# controller2_5.net
KiCad netlist of a schematic drawn in EAGLE
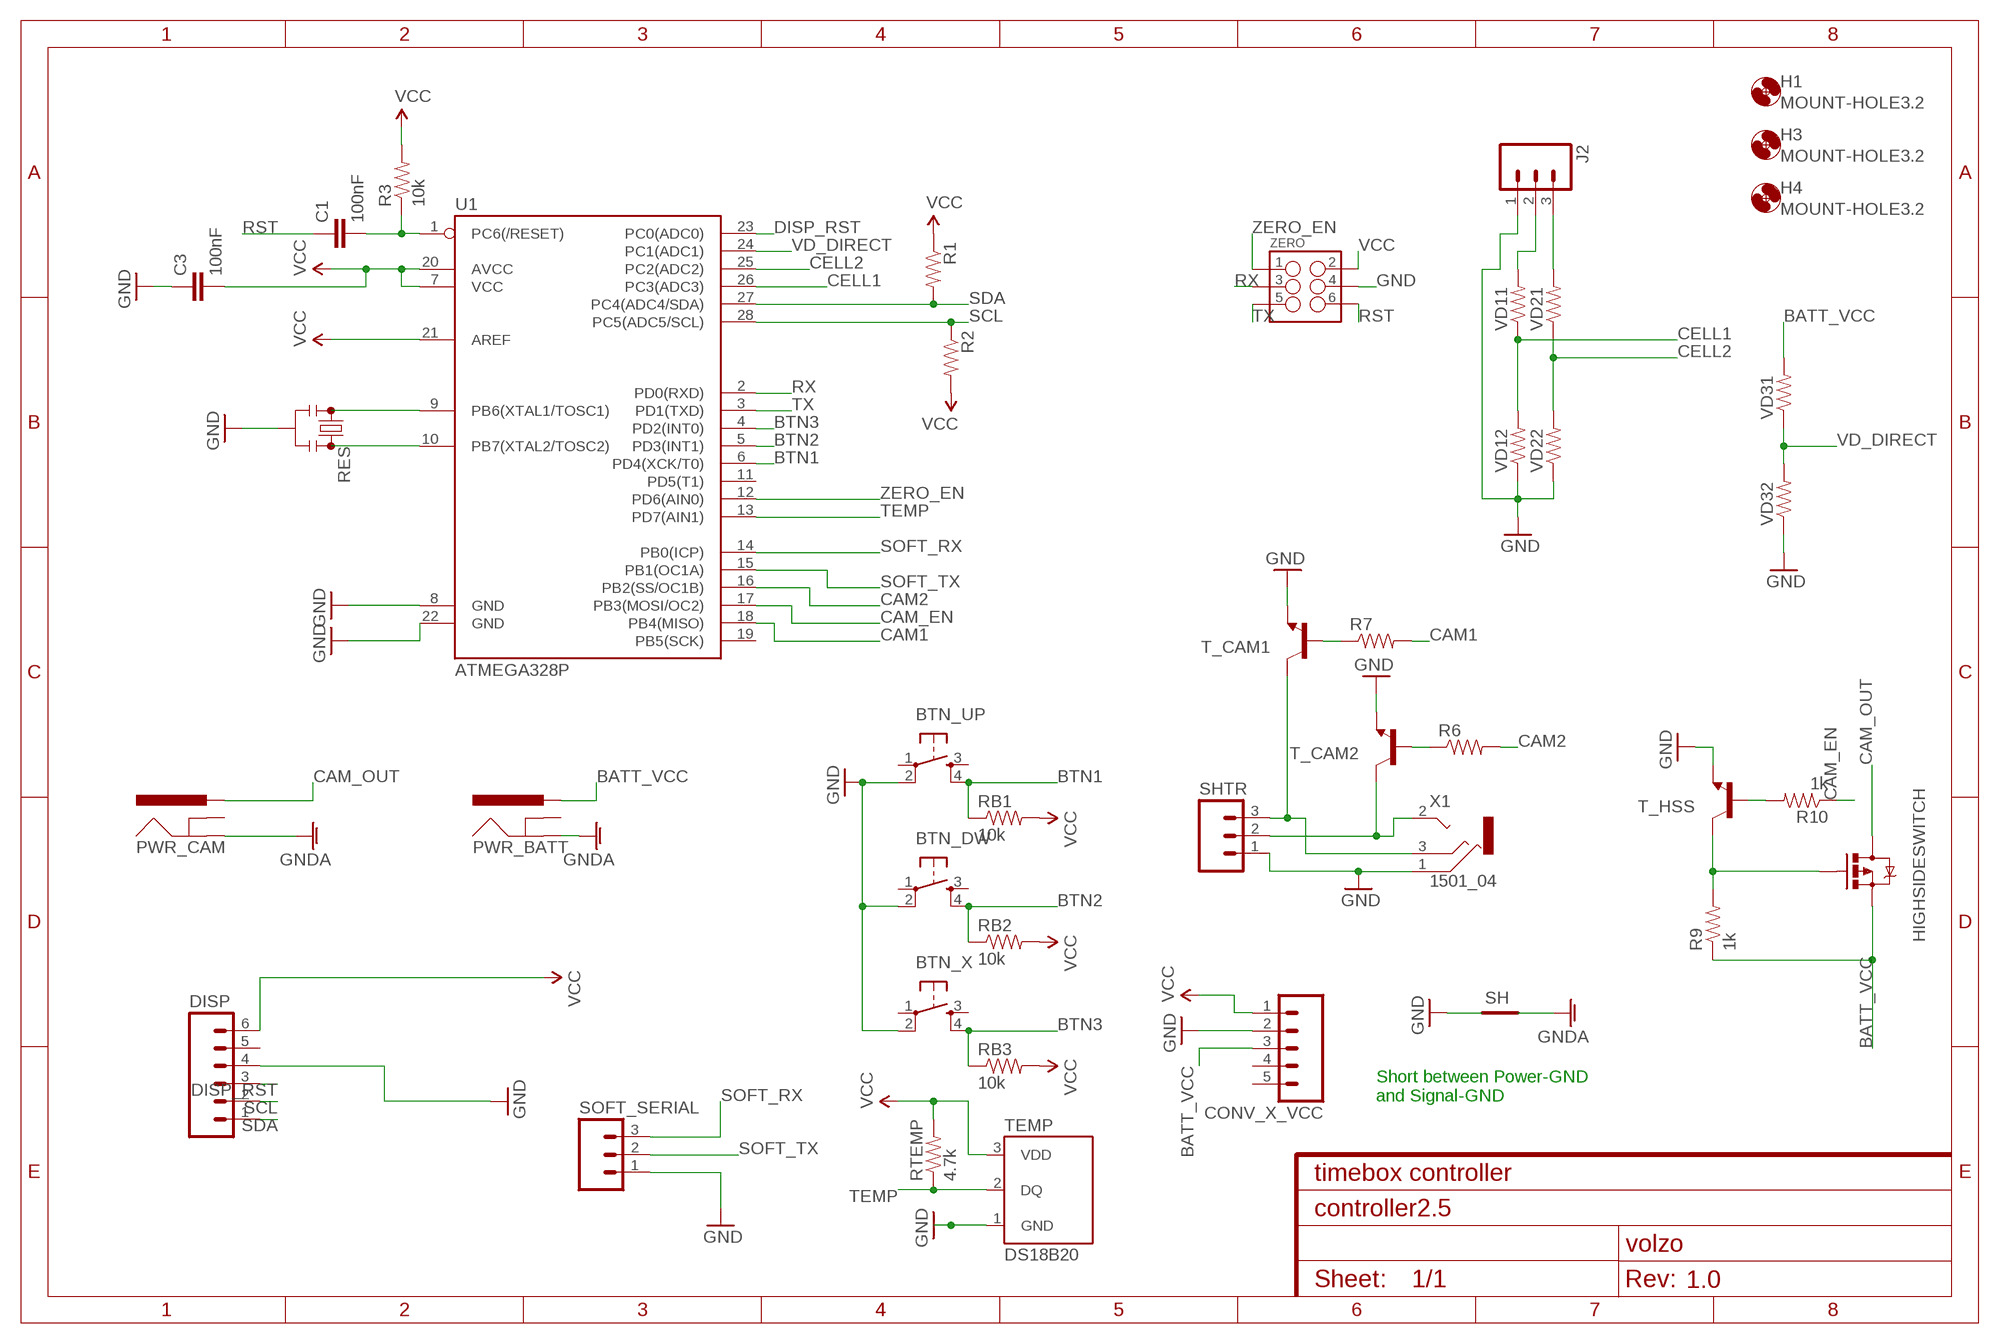
[diagram p0: schematic, sheet 1]

(export (version "E")
  (design (tool "Eeschema 10.0.6"))
  (components
    (comp (ref "BTN_DW")
      (value "TAC_SWITCHPTH")
      (footprint "eagle-import:TACTILE-PTH")
      (libsource (lib "eagle-import") (part "TAC_SWITCHPTH"))
    )
    (comp (ref "BTN_UP")
      (value "TAC_SWITCHPTH")
      (footprint "eagle-import:TACTILE-PTH")
      (libsource (lib "eagle-import") (part "TAC_SWITCHPTH"))
    )
    (comp (ref "BTN_X")
      (value "TAC_SWITCHPTH")
      (footprint "eagle-import:TACTILE-PTH")
      (libsource (lib "eagle-import") (part "TAC_SWITCHPTH"))
    )
    (comp (ref "C1")
      (value "100nF")
      (footprint "eagle-import:CAP-PTH-SMALL")
      (libsource (lib "eagle-import") (part "CAPPTH"))
    )
    (comp (ref "C3")
      (value "100nF")
      (footprint "eagle-import:CAP-PTH-SMALL")
      (libsource (lib "eagle-import") (part "CAPPTH"))
    )
    (comp (ref "CONV_X_VCC")
      (value "M05LOCK")
      (footprint "eagle-import:1X05_LOCK")
      (libsource (lib "eagle-import") (part "M05LOCK"))
    )
    (comp (ref "DISP")
      (value "M06FEMALE_LOCK")
      (footprint "eagle-import:1X06_FEMALE_LOCK.010")
      (libsource (lib "eagle-import") (part "M06FEMALE_LOCK"))
    )
    (comp (ref "H1")
      (value "MOUNT-HOLE3.2")
      (footprint "eagle-import:3,2")
      (libsource (lib "eagle-import") (part "MOUNT-HOLE3.2"))
    )
    (comp (ref "H3")
      (value "MOUNT-HOLE3.2")
      (footprint "eagle-import:3,2")
      (libsource (lib "eagle-import") (part "MOUNT-HOLE3.2"))
    )
    (comp (ref "H4")
      (value "MOUNT-HOLE3.2")
      (footprint "eagle-import:3,2")
      (libsource (lib "eagle-import") (part "MOUNT-HOLE3.2"))
    )
    (comp (ref "HIGHSIDESWITCH")
      (value "MOSFET-PCHANNELNDP6020P_20V_24A_LOW_VGS_TH")
      (footprint "eagle-import:TO220V")
      (libsource (lib "eagle-import") (part "MOSFET-PCHANNELNDP6020P_20V_24A_LOW_VGS_TH"))
    )
    (comp (ref "J2")
      (value "M03LOCK")
      (footprint "eagle-import:1X03_LOCK")
      (libsource (lib "eagle-import") (part "M03LOCK"))
    )
    (comp (ref "PWR_BATT")
      (value "POWER_JACKPTH_BREAD")
      (footprint "eagle-import:POWER_JACK_PTH_BREAD")
      (libsource (lib "eagle-import") (part "POWER_JACKPTH_BREAD"))
    )
    (comp (ref "PWR_CAM")
      (value "POWER_JACKPTH_BREAD")
      (footprint "eagle-import:POWER_JACK_PTH_BREAD")
      (libsource (lib "eagle-import") (part "POWER_JACKPTH_BREAD"))
    )
    (comp (ref "R1")
      (value "RESISTORAXIAL-0.3")
      (footprint "eagle-import:AXIAL-0.3")
      (libsource (lib "eagle-import") (part "RESISTORAXIAL-0.3"))
    )
    (comp (ref "R2")
      (value "RESISTORAXIAL-0.3")
      (footprint "eagle-import:AXIAL-0.3")
      (libsource (lib "eagle-import") (part "RESISTORAXIAL-0.3"))
    )
    (comp (ref "R3")
      (value "10k")
      (footprint "eagle-import:AXIAL-0.3")
      (libsource (lib "eagle-import") (part "RESISTORAXIAL-0.3"))
    )
    (comp (ref "R6")
      (value "RESISTORAXIAL-0.3")
      (footprint "eagle-import:AXIAL-0.3")
      (libsource (lib "eagle-import") (part "RESISTORAXIAL-0.3"))
    )
    (comp (ref "R7")
      (value "RESISTORAXIAL-0.3")
      (footprint "eagle-import:AXIAL-0.3")
      (libsource (lib "eagle-import") (part "RESISTORAXIAL-0.3"))
    )
    (comp (ref "R9")
      (value "1k")
      (footprint "eagle-import:AXIAL-0.3")
      (libsource (lib "eagle-import") (part "RESISTORAXIAL-0.3"))
    )
    (comp (ref "R10")
      (value "1k")
      (footprint "eagle-import:AXIAL-0.3")
      (libsource (lib "eagle-import") (part "RESISTORAXIAL-0.3"))
    )
    (comp (ref "RB1")
      (value "10k")
      (footprint "eagle-import:AXIAL-0.3")
      (libsource (lib "eagle-import") (part "RESISTORAXIAL-0.3"))
    )
    (comp (ref "RB2")
      (value "10k")
      (footprint "eagle-import:AXIAL-0.3")
      (libsource (lib "eagle-import") (part "RESISTORAXIAL-0.3"))
    )
    (comp (ref "RB3")
      (value "10k")
      (footprint "eagle-import:AXIAL-0.3")
      (libsource (lib "eagle-import") (part "RESISTORAXIAL-0.3"))
    )
    (comp (ref "RES")
      (value "RESONATORPTH")
      (footprint "eagle-import:RESONATOR-PTH")
      (libsource (lib "eagle-import") (part "RESONATORPTH"))
    )
    (comp (ref "RTEMP")
      (value "4.7k")
      (footprint "eagle-import:AXIAL-0.3")
      (libsource (lib "eagle-import") (part "RESISTORAXIAL-0.3"))
    )
    (comp (ref "SH")
      (value "SHORT-HT5")
      (footprint "eagle-import:SHORT_TOP-50")
      (libsource (lib "eagle-import") (part "SHORT-HT5"))
    )
    (comp (ref "SHTR")
      (value "M03LOCK")
      (footprint "eagle-import:1X03_LOCK")
      (libsource (lib "eagle-import") (part "M03LOCK"))
    )
    (comp (ref "SOFT_SERIAL")
      (value "M03LOCK")
      (footprint "eagle-import:1X03_LOCK")
      (libsource (lib "eagle-import") (part "M03LOCK"))
    )
    (comp (ref "TEMP")
      (value "DS18B20")
      (footprint "eagle-import:TO-92-AMMO")
      (libsource (lib "eagle-import") (part "DS18B20"))
    )
    (comp (ref "T_CAM1")
      (value "TRANSISTOR_NPN2N3904")
      (footprint "eagle-import:TO-92")
      (libsource (lib "eagle-import") (part "TRANSISTOR_NPN2N3904"))
    )
    (comp (ref "T_CAM2")
      (value "TRANSISTOR_NPN2N3904")
      (footprint "eagle-import:TO-92")
      (libsource (lib "eagle-import") (part "TRANSISTOR_NPN2N3904"))
    )
    (comp (ref "T_HSS")
      (value "TRANSISTOR_NPN2N3904")
      (footprint "eagle-import:TO-92")
      (libsource (lib "eagle-import") (part "TRANSISTOR_NPN2N3904"))
    )
    (comp (ref "U1")
      (value "ATMEGA328P")
      (footprint "eagle-import:DIL28-3")
      (libsource (lib "eagle-import") (part "ATMEGA328P_PDIP"))
    )
    (comp (ref "VD11")
      (value "RESISTORAXIAL-0.3")
      (footprint "eagle-import:AXIAL-0.3")
      (libsource (lib "eagle-import") (part "RESISTORAXIAL-0.3"))
    )
    (comp (ref "VD12")
      (value "RESISTORAXIAL-0.3")
      (footprint "eagle-import:AXIAL-0.3")
      (libsource (lib "eagle-import") (part "RESISTORAXIAL-0.3"))
    )
    (comp (ref "VD21")
      (value "RESISTORAXIAL-0.3")
      (footprint "eagle-import:AXIAL-0.3")
      (libsource (lib "eagle-import") (part "RESISTORAXIAL-0.3"))
    )
    (comp (ref "VD22")
      (value "RESISTORAXIAL-0.3")
      (footprint "eagle-import:AXIAL-0.3")
      (libsource (lib "eagle-import") (part "RESISTORAXIAL-0.3"))
    )
    (comp (ref "VD31")
      (value "RESISTORAXIAL-0.3")
      (footprint "eagle-import:AXIAL-0.3")
      (libsource (lib "eagle-import") (part "RESISTORAXIAL-0.3"))
    )
    (comp (ref "VD32")
      (value "RESISTORAXIAL-0.3")
      (footprint "eagle-import:AXIAL-0.3")
      (libsource (lib "eagle-import") (part "RESISTORAXIAL-0.3"))
    )
    (comp (ref "X1")
      (value "1501_04")
      (footprint "eagle-import:1501_05")
      (libsource (lib "eagle-import") (part "1501_04"))
    )
    (comp (ref "ZERO")
      (value "M03X2FEMALE")
      (footprint "eagle-import:2X3")
      (libsource (lib "eagle-import") (part "M03X2FEMALE"))
    )
  )
  (nets
    (net (code "1") (name "/BATT_VCC") (class "Default")
      (node (ref "CONV_X_VCC") (pin "3") (pinfunction "3_3") (pintype "passive"))
      (node (ref "HIGHSIDESWITCH") (pin "3") (pinfunction "S_3") (pintype "passive"))
      (node (ref "PWR_BATT") (pin "PWR") (pinfunction "PWR_PWR") (pintype "bidirectional"))
      (node (ref "R9") (pin "P$1") (pinfunction "1_P$1") (pintype "passive"))
      (node (ref "VD31") (pin "P$2") (pinfunction "2_P$2") (pintype "passive"))
    )
    (net (code "2") (name "/BTN1") (class "Default")
      (node (ref "BTN_UP") (pin "4") (pinfunction "4_4") (pintype "passive"))
      (node (ref "RB1") (pin "P$1") (pinfunction "1_P$1") (pintype "passive"))
      (node (ref "U1") (pin "6") (pinfunction "PD4(XCK/T0)_6") (pintype "bidirectional"))
    )
    (net (code "3") (name "/BTN2") (class "Default")
      (node (ref "BTN_DW") (pin "4") (pinfunction "4_4") (pintype "passive"))
      (node (ref "RB2") (pin "P$1") (pinfunction "1_P$1") (pintype "passive"))
      (node (ref "U1") (pin "5") (pinfunction "PD3(INT1)_5") (pintype "bidirectional"))
    )
    (net (code "4") (name "/BTN3") (class "Default")
      (node (ref "BTN_X") (pin "4") (pinfunction "4_4") (pintype "passive"))
      (node (ref "RB3") (pin "P$1") (pinfunction "1_P$1") (pintype "passive"))
      (node (ref "U1") (pin "4") (pinfunction "PD2(INT0)_4") (pintype "bidirectional"))
    )
    (net (code "5") (name "/CAM1") (class "Default")
      (node (ref "R7") (pin "P$2") (pinfunction "2_P$2") (pintype "passive"))
      (node (ref "U1") (pin "18") (pinfunction "PB4(MISO)_18") (pintype "bidirectional"))
    )
    (net (code "6") (name "/CAM2") (class "Default")
      (node (ref "R6") (pin "P$2") (pinfunction "2_P$2") (pintype "passive"))
      (node (ref "U1") (pin "16") (pinfunction "PB2(SS/OC1B)_16") (pintype "bidirectional"))
    )
    (net (code "7") (name "/CAM_EN") (class "Default")
      (node (ref "R10") (pin "P$1") (pinfunction "1_P$1") (pintype "passive"))
      (node (ref "U1") (pin "17") (pinfunction "PB3(MOSI/OC2)_17") (pintype "bidirectional"))
    )
    (net (code "8") (name "/CAM_OUT") (class "Default")
      (node (ref "HIGHSIDESWITCH") (pin "2") (pinfunction "D_2") (pintype "passive"))
      (node (ref "PWR_CAM") (pin "PWR") (pinfunction "PWR_PWR") (pintype "bidirectional"))
    )
    (net (code "9") (name "/CELL1") (class "Default")
      (node (ref "U1") (pin "26") (pinfunction "PC3(ADC3)_26") (pintype "bidirectional"))
      (node (ref "VD11") (pin "P$1") (pinfunction "1_P$1") (pintype "passive"))
      (node (ref "VD12") (pin "P$2") (pinfunction "2_P$2") (pintype "passive"))
    )
    (net (code "10") (name "/CELL2") (class "Default")
      (node (ref "U1") (pin "25") (pinfunction "PC2(ADC2)_25") (pintype "bidirectional"))
      (node (ref "VD21") (pin "P$1") (pinfunction "1_P$1") (pintype "passive"))
      (node (ref "VD22") (pin "P$2") (pinfunction "2_P$2") (pintype "passive"))
    )
    (net (code "11") (name "/DISP_RST") (class "Default")
      (node (ref "DISP") (pin "3") (pinfunction "3_3") (pintype "passive"))
      (node (ref "U1") (pin "23") (pinfunction "PC0(ADC0)_23") (pintype "bidirectional"))
    )
    (net (code "12") (name "/RST") (class "Default")
      (node (ref "C1") (pin "1") (pinfunction "1_1") (pintype "passive"))
      (node (ref "ZERO") (pin "6") (pinfunction "6_6") (pintype "bidirectional"))
    )
    (net (code "13") (name "/RX") (class "Default")
      (node (ref "U1") (pin "2") (pinfunction "PD0(RXD)_2") (pintype "bidirectional"))
      (node (ref "ZERO") (pin "3") (pinfunction "3_3") (pintype "bidirectional"))
    )
    (net (code "14") (name "/SCL") (class "Default")
      (node (ref "DISP") (pin "2") (pinfunction "2_2") (pintype "passive"))
      (node (ref "R2") (pin "P$1") (pinfunction "1_P$1") (pintype "passive"))
      (node (ref "U1") (pin "28") (pinfunction "PC5(ADC5/SCL)_28") (pintype "bidirectional"))
    )
    (net (code "15") (name "/SDA") (class "Default")
      (node (ref "DISP") (pin "1") (pinfunction "1_1") (pintype "passive"))
      (node (ref "R1") (pin "P$2") (pinfunction "2_P$2") (pintype "passive"))
      (node (ref "U1") (pin "27") (pinfunction "PC4(ADC4/SDA)_27") (pintype "bidirectional"))
    )
    (net (code "16") (name "/SOFT_RX") (class "Default")
      (node (ref "SOFT_SERIAL") (pin "3") (pinfunction "3_3") (pintype "passive"))
      (node (ref "U1") (pin "14") (pinfunction "PB0(ICP)_14") (pintype "bidirectional"))
    )
    (net (code "17") (name "/SOFT_TX") (class "Default")
      (node (ref "SOFT_SERIAL") (pin "2") (pinfunction "2_2") (pintype "passive"))
      (node (ref "U1") (pin "15") (pinfunction "PB1(OC1A)_15") (pintype "bidirectional"))
    )
    (net (code "18") (name "/TEMP") (class "Default")
      (node (ref "RTEMP") (pin "P$1") (pinfunction "1_P$1") (pintype "passive"))
      (node (ref "TEMP") (pin "2") (pinfunction "DQ_2") (pintype "bidirectional"))
      (node (ref "U1") (pin "13") (pinfunction "PD7(AIN1)_13") (pintype "bidirectional"))
    )
    (net (code "19") (name "/TX") (class "Default")
      (node (ref "U1") (pin "3") (pinfunction "PD1(TXD)_3") (pintype "bidirectional"))
      (node (ref "ZERO") (pin "5") (pinfunction "5_5") (pintype "bidirectional"))
    )
    (net (code "20") (name "/VD_DIRECT") (class "Default")
      (node (ref "U1") (pin "24") (pinfunction "PC1(ADC1)_24") (pintype "bidirectional"))
      (node (ref "VD31") (pin "P$1") (pinfunction "1_P$1") (pintype "passive"))
      (node (ref "VD32") (pin "P$2") (pinfunction "2_P$2") (pintype "passive"))
    )
    (net (code "21") (name "/ZERO_EN") (class "Default")
      (node (ref "U1") (pin "12") (pinfunction "PD6(AIN0)_12") (pintype "bidirectional"))
      (node (ref "ZERO") (pin "1") (pinfunction "1_1") (pintype "bidirectional"))
    )
    (net (code "22") (name "GND") (class "Default")
      (node (ref "BTN_DW") (pin "2") (pinfunction "2_2") (pintype "passive"))
      (node (ref "BTN_UP") (pin "2") (pinfunction "2_2") (pintype "passive"))
      (node (ref "BTN_X") (pin "2") (pinfunction "2_2") (pintype "passive"))
      (node (ref "C3") (pin "1") (pinfunction "1_1") (pintype "passive"))
      (node (ref "CONV_X_VCC") (pin "2") (pinfunction "2_2") (pintype "passive"))
      (node (ref "DISP") (pin "4") (pinfunction "4_4") (pintype "passive"))
      (node (ref "J2") (pin "1") (pinfunction "1_1") (pintype "passive"))
      (node (ref "RES") (pin "2") (pinfunction "2_2") (pintype "passive"))
      (node (ref "SH") (pin "1") (pinfunction "P$1_1") (pintype "bidirectional"))
      (node (ref "SHTR") (pin "1") (pinfunction "1_1") (pintype "passive"))
      (node (ref "SOFT_SERIAL") (pin "1") (pinfunction "1_1") (pintype "passive"))
      (node (ref "TEMP") (pin "1") (pinfunction "GND_1") (pintype "power_in"))
      (node (ref "T_CAM1") (pin "1") (pinfunction "E_1") (pintype "passive"))
      (node (ref "T_CAM2") (pin "1") (pinfunction "E_1") (pintype "passive"))
      (node (ref "T_HSS") (pin "1") (pinfunction "E_1") (pintype "passive"))
      (node (ref "U1") (pin "22") (pinfunction "GND_22") (pintype "bidirectional"))
      (node (ref "U1") (pin "8") (pinfunction "GND_8") (pintype "bidirectional"))
      (node (ref "VD12") (pin "P$1") (pinfunction "1_P$1") (pintype "passive"))
      (node (ref "VD22") (pin "P$1") (pinfunction "1_P$1") (pintype "passive"))
      (node (ref "VD32") (pin "P$1") (pinfunction "1_P$1") (pintype "passive"))
      (node (ref "X1") (pin "1") (pinfunction "1_1") (pintype "passive"))
      (node (ref "ZERO") (pin "4") (pinfunction "4_4") (pintype "bidirectional"))
    )
    (net (code "23") (name "GNDA") (class "Default")
      (node (ref "PWR_BATT") (pin "GND") (pinfunction "GND_GND") (pintype "bidirectional"))
      (node (ref "PWR_CAM") (pin "GND") (pinfunction "GND_GND") (pintype "bidirectional"))
      (node (ref "SH") (pin "2") (pinfunction "P$2_2") (pintype "bidirectional"))
    )
    (net (code "24") (name "Net-(HIGHSIDESWITCH-G)") (class "Default")
      (node (ref "HIGHSIDESWITCH") (pin "1") (pinfunction "G_1") (pintype "passive"))
      (node (ref "R9") (pin "P$2") (pinfunction "2_P$2") (pintype "passive"))
      (node (ref "T_HSS") (pin "3") (pinfunction "C_3") (pintype "passive"))
    )
    (net (code "25") (name "Net-(R3-1)") (class "Default")
      (node (ref "C1") (pin "2") (pinfunction "2_2") (pintype "passive"))
      (node (ref "R3") (pin "P$1") (pinfunction "1_P$1") (pintype "passive"))
      (node (ref "U1") (pin "1") (pinfunction "PC6(/RESET)_1") (pintype "bidirectional"))
    )
    (net (code "26") (name "Net-(R6-1)") (class "Default")
      (node (ref "R6") (pin "P$1") (pinfunction "1_P$1") (pintype "passive"))
      (node (ref "T_CAM2") (pin "2") (pinfunction "B_2") (pintype "passive"))
    )
    (net (code "27") (name "Net-(R7-1)") (class "Default")
      (node (ref "R7") (pin "P$1") (pinfunction "1_P$1") (pintype "passive"))
      (node (ref "T_CAM1") (pin "2") (pinfunction "B_2") (pintype "passive"))
    )
    (net (code "28") (name "Net-(R10-2)") (class "Default")
      (node (ref "R10") (pin "P$2") (pinfunction "2_P$2") (pintype "passive"))
      (node (ref "T_HSS") (pin "2") (pinfunction "B_2") (pintype "passive"))
    )
    (net (code "29") (name "Net-(T_CAM1-C)") (class "Default")
      (node (ref "SHTR") (pin "3") (pinfunction "3_3") (pintype "passive"))
      (node (ref "T_CAM1") (pin "3") (pinfunction "C_3") (pintype "passive"))
      (node (ref "X1") (pin "3") (pinfunction "3_3") (pintype "passive"))
    )
    (net (code "30") (name "Net-(T_CAM2-C)") (class "Default")
      (node (ref "SHTR") (pin "2") (pinfunction "2_2") (pintype "passive"))
      (node (ref "T_CAM2") (pin "3") (pinfunction "C_3") (pintype "passive"))
      (node (ref "X1") (pin "2") (pinfunction "2_2") (pintype "passive"))
    )
    (net (code "31") (name "Net-(U1-PB6(XTAL1{slash}TOSC1))") (class "Default")
      (node (ref "RES") (pin "1") (pinfunction "1_1") (pintype "passive"))
      (node (ref "U1") (pin "9") (pinfunction "PB6(XTAL1/TOSC1)_9") (pintype "bidirectional"))
    )
    (net (code "32") (name "Net-(U1-PB7(XTAL2{slash}TOSC2))") (class "Default")
      (node (ref "RES") (pin "3") (pinfunction "3_3") (pintype "passive"))
      (node (ref "U1") (pin "10") (pinfunction "PB7(XTAL2/TOSC2)_10") (pintype "bidirectional"))
    )
    (net (code "33") (name "Net-(VD11-2)") (class "Default")
      (node (ref "J2") (pin "2") (pinfunction "2_2") (pintype "passive"))
      (node (ref "VD11") (pin "P$2") (pinfunction "2_P$2") (pintype "passive"))
    )
    (net (code "34") (name "Net-(VD21-2)") (class "Default")
      (node (ref "J2") (pin "3") (pinfunction "3_3") (pintype "passive"))
      (node (ref "VD21") (pin "P$2") (pinfunction "2_P$2") (pintype "passive"))
    )
    (net (code "35") (name "VCC") (class "Default")
      (node (ref "C3") (pin "2") (pinfunction "2_2") (pintype "passive"))
      (node (ref "CONV_X_VCC") (pin "1") (pinfunction "1_1") (pintype "passive"))
      (node (ref "DISP") (pin "6") (pinfunction "6_6") (pintype "passive"))
      (node (ref "R1") (pin "P$1") (pinfunction "1_P$1") (pintype "passive"))
      (node (ref "R2") (pin "P$2") (pinfunction "2_P$2") (pintype "passive"))
      (node (ref "R3") (pin "P$2") (pinfunction "2_P$2") (pintype "passive"))
      (node (ref "RB1") (pin "P$2") (pinfunction "2_P$2") (pintype "passive"))
      (node (ref "RB2") (pin "P$2") (pinfunction "2_P$2") (pintype "passive"))
      (node (ref "RB3") (pin "P$2") (pinfunction "2_P$2") (pintype "passive"))
      (node (ref "RTEMP") (pin "P$2") (pinfunction "2_P$2") (pintype "passive"))
      (node (ref "TEMP") (pin "3") (pinfunction "VDD_3") (pintype "power_in"))
      (node (ref "U1") (pin "20") (pinfunction "AVCC_20") (pintype "bidirectional"))
      (node (ref "U1") (pin "21") (pinfunction "AREF_21") (pintype "bidirectional"))
      (node (ref "U1") (pin "7") (pinfunction "VCC_7") (pintype "bidirectional"))
      (node (ref "ZERO") (pin "2") (pinfunction "2_2") (pintype "bidirectional"))
    )
    (net (code "36") (name "unconnected-(BTN_DW-Pad1)") (class "Default")
      (node (ref "BTN_DW") (pin "1") (pinfunction "1_1") (pintype "passive"))
    )
    (net (code "37") (name "unconnected-(BTN_DW-Pad3)") (class "Default")
      (node (ref "BTN_DW") (pin "3") (pinfunction "3_3") (pintype "passive"))
    )
    (net (code "38") (name "unconnected-(BTN_UP-Pad1)") (class "Default")
      (node (ref "BTN_UP") (pin "1") (pinfunction "1_1") (pintype "passive"))
    )
    (net (code "39") (name "unconnected-(BTN_UP-Pad3)") (class "Default")
      (node (ref "BTN_UP") (pin "3") (pinfunction "3_3") (pintype "passive"))
    )
    (net (code "40") (name "unconnected-(BTN_X-Pad1)") (class "Default")
      (node (ref "BTN_X") (pin "1") (pinfunction "1_1") (pintype "passive"))
    )
    (net (code "41") (name "unconnected-(BTN_X-Pad3)") (class "Default")
      (node (ref "BTN_X") (pin "3") (pinfunction "3_3") (pintype "passive"))
    )
    (net (code "42") (name "unconnected-(CONV_X_VCC-Pad4)") (class "Default")
      (node (ref "CONV_X_VCC") (pin "4") (pinfunction "4_4") (pintype "passive"))
    )
    (net (code "43") (name "unconnected-(CONV_X_VCC-Pad5)") (class "Default")
      (node (ref "CONV_X_VCC") (pin "5") (pinfunction "5_5") (pintype "passive"))
    )
    (net (code "44") (name "unconnected-(DISP-Pad5)") (class "Default")
      (node (ref "DISP") (pin "5") (pinfunction "5_5") (pintype "passive"))
    )
    (net (code "45") (name "unconnected-(PWR_BATT-PadGNDBREAK)") (class "Default")
      (node (ref "PWR_BATT") (pin "GNDBREAK") (pinfunction "GNDBREAK_GNDBREAK") (pintype "bidirectional"))
    )
    (net (code "46") (name "unconnected-(PWR_CAM-PadGNDBREAK)") (class "Default")
      (node (ref "PWR_CAM") (pin "GNDBREAK") (pinfunction "GNDBREAK_GNDBREAK") (pintype "bidirectional"))
    )
    (net (code "47") (name "unconnected-(U1-PB5(SCK)-Pad19)") (class "Default")
      (node (ref "U1") (pin "19") (pinfunction "PB5(SCK)_19") (pintype "bidirectional"))
    )
    (net (code "48") (name "unconnected-(U1-PD5(T1)-Pad11)") (class "Default")
      (node (ref "U1") (pin "11") (pinfunction "PD5(T1)_11") (pintype "bidirectional"))
    )
  )
)
